# IMX8_INTERFACE.net
KiCad netlist of a schematic drawn in Altium Designer
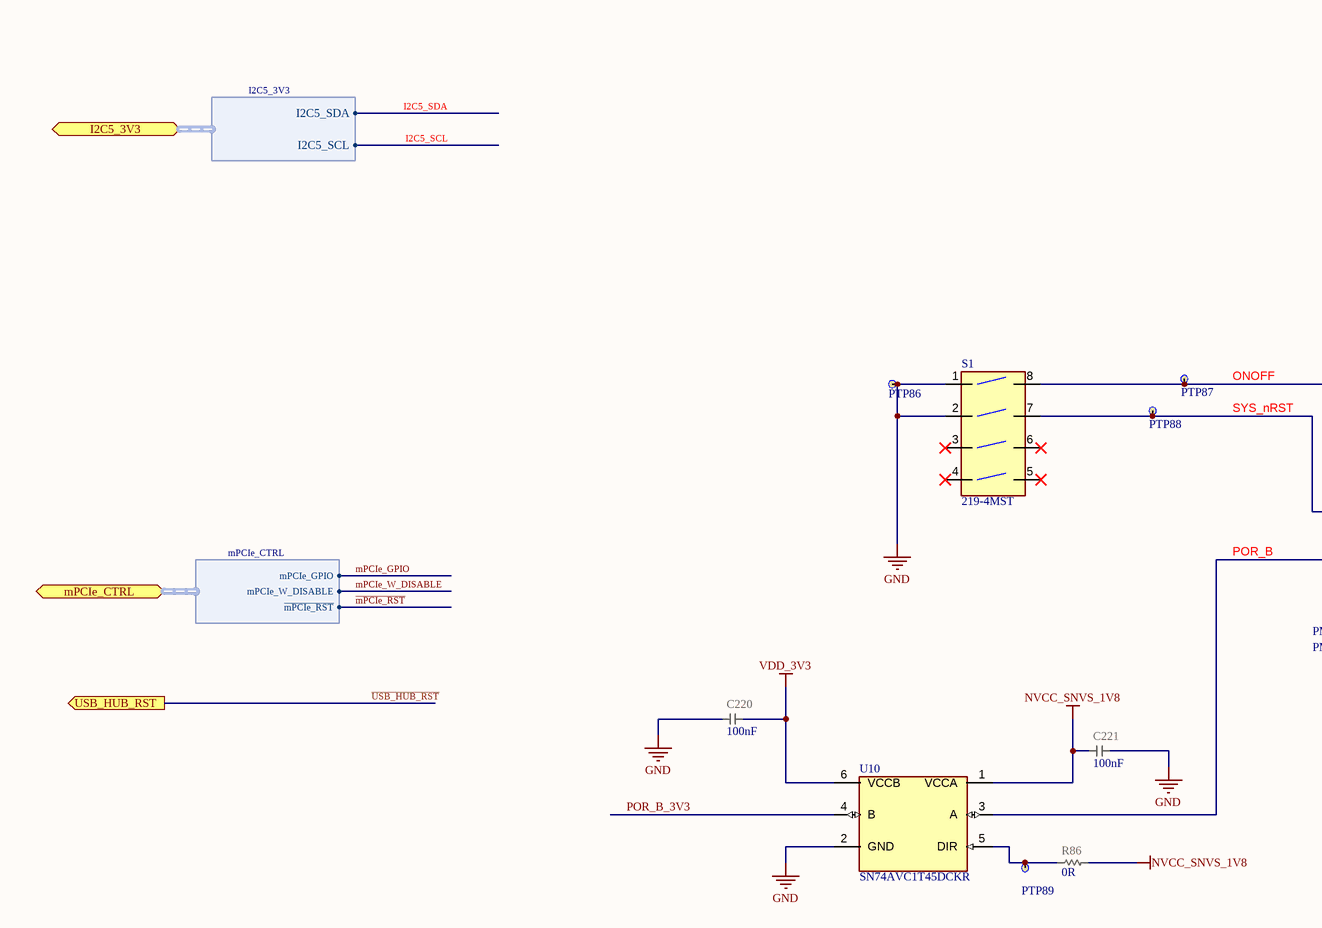
[diagram p0: IMX8_INTERFACE.SchDoc, top left]
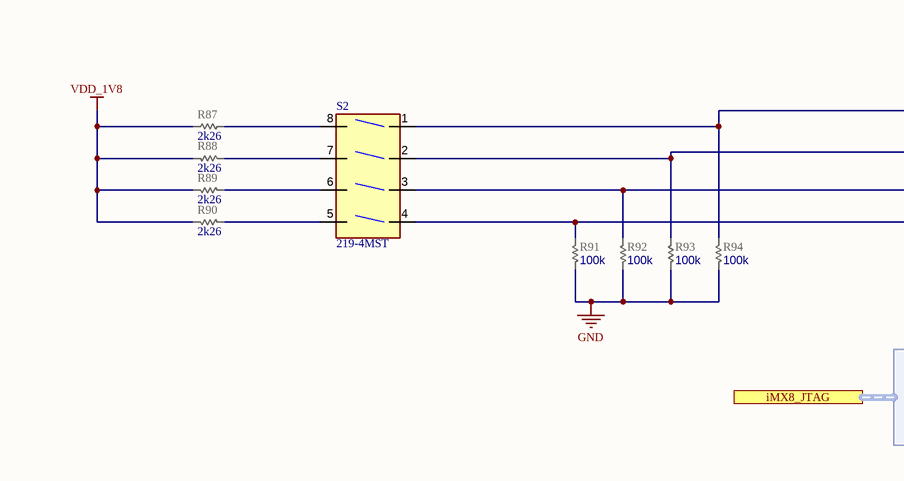
[diagram p1: IMX8_INTERFACE.SchDoc, bottom left]
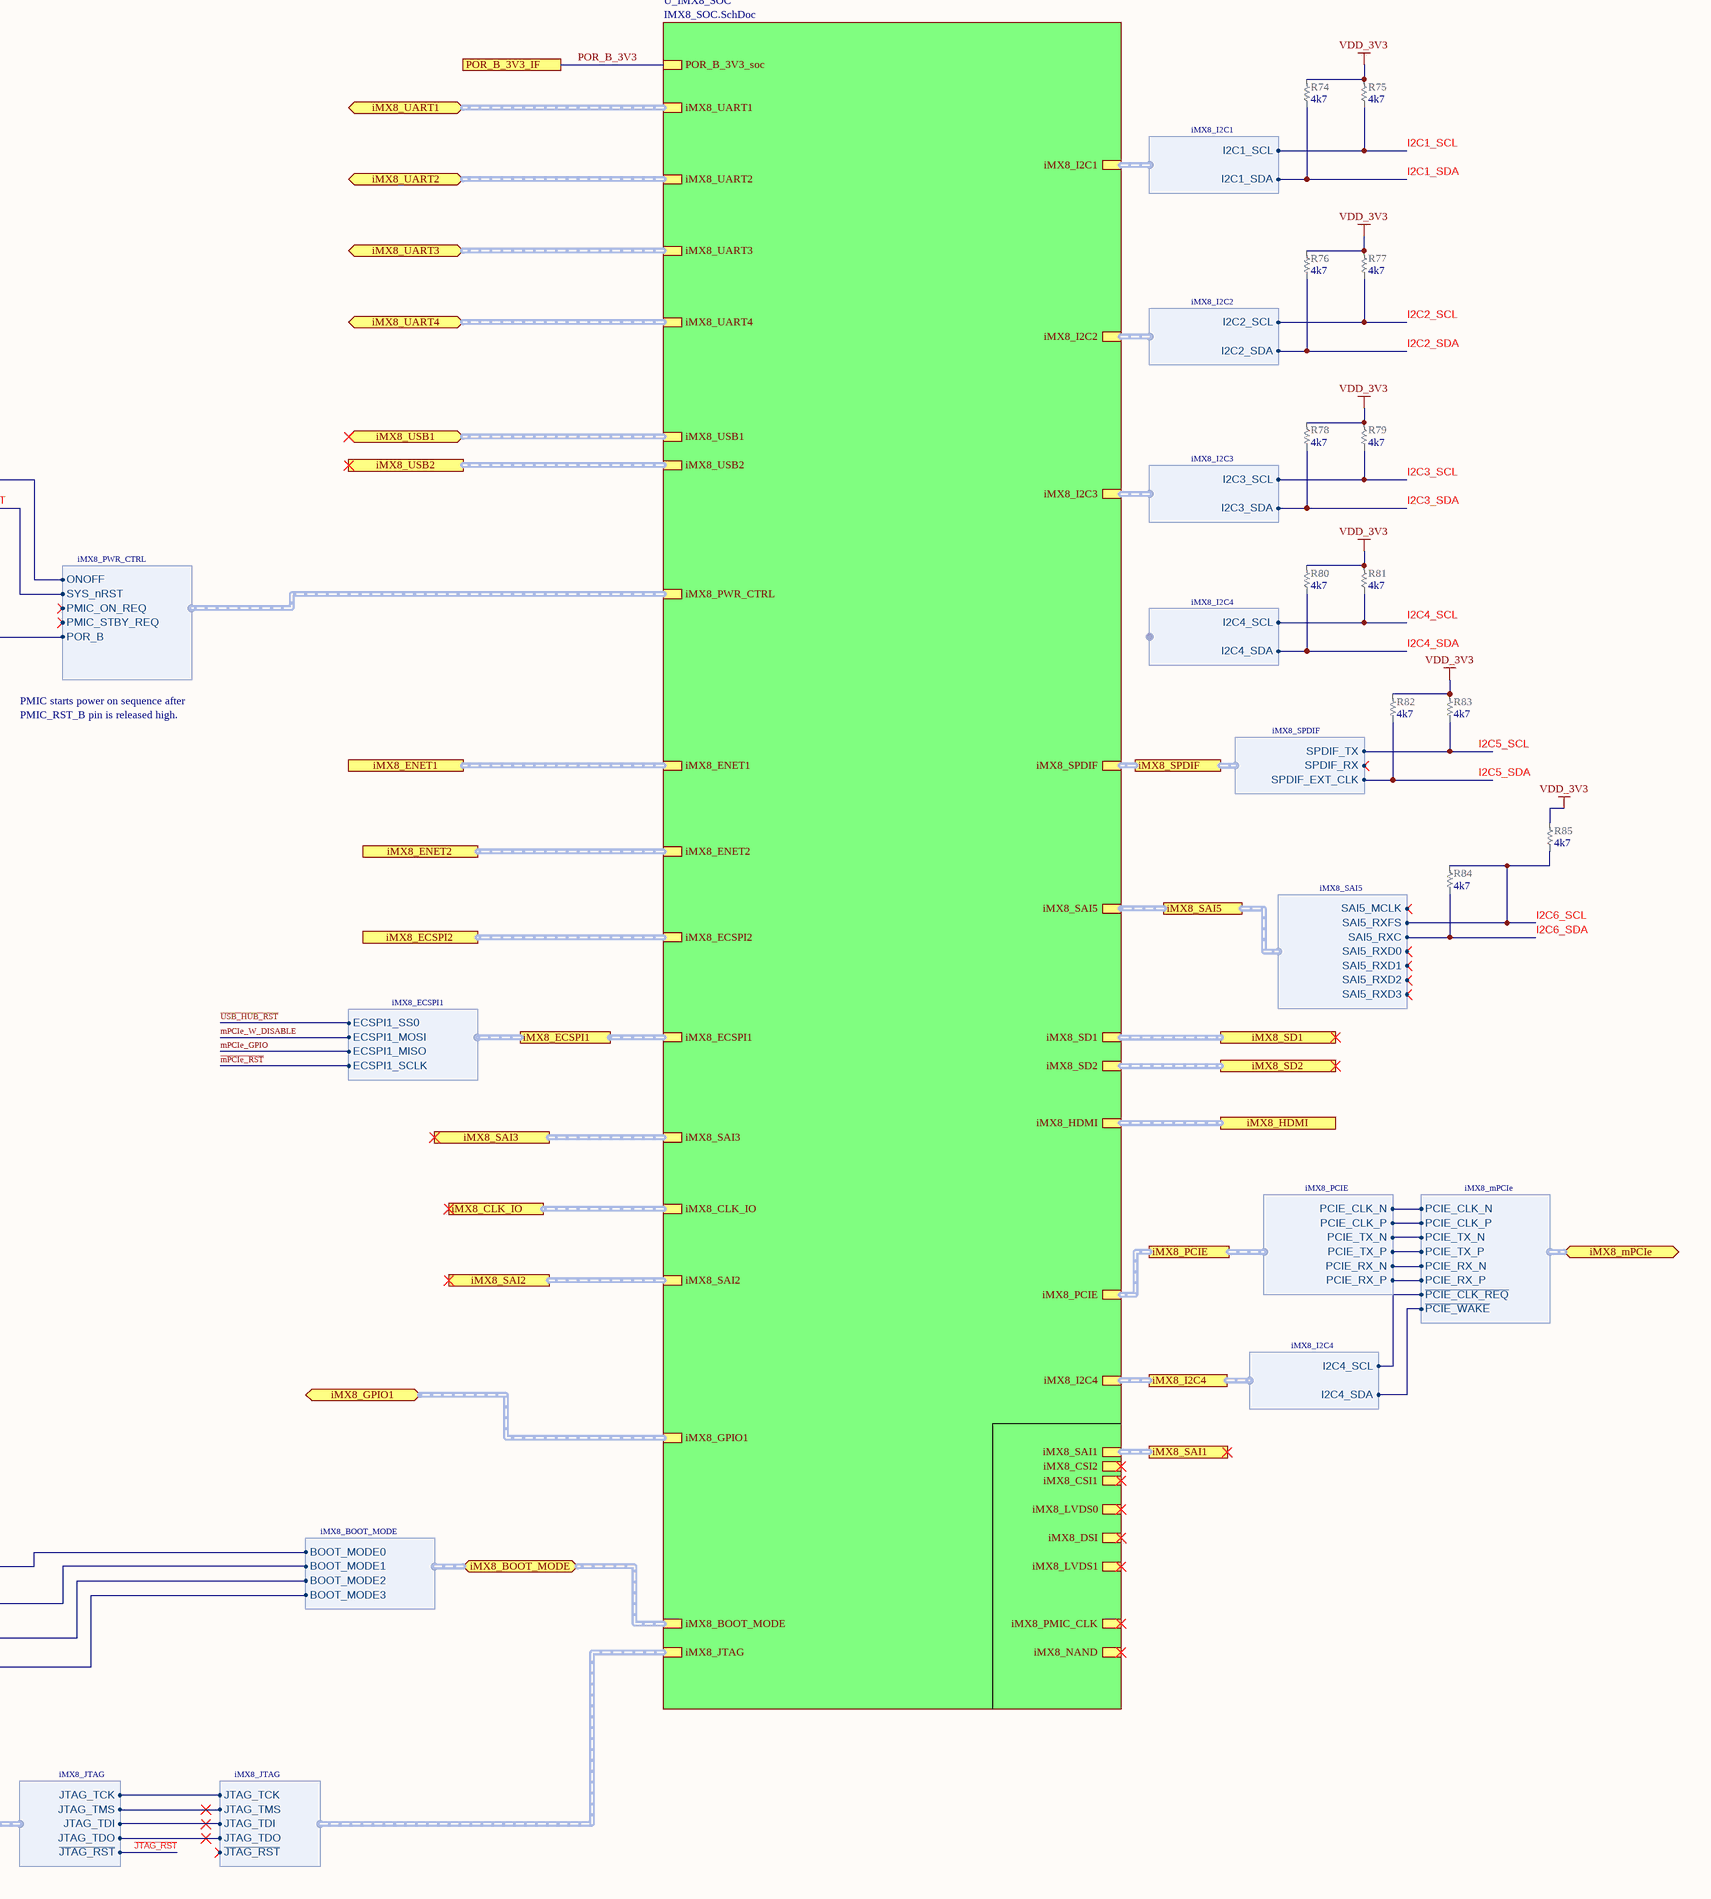
[diagram p2: IMX8_INTERFACE.SchDoc, bottom right]

(export (version "E")
  (design (tool "Eeschema 10.0.6"))
  (components
    (comp (ref "C220")
      (value "100nF")
      (footprint "CAP_0201_UN1Q")
      (description "CAP")
      (fields (field (name "PART NUMBER") "GRM033C71C104KE14D") (field (name "MANUFACTURER") "Murata"))
      (libsource (lib "robo_cam") (part "CMP-001-000385-16"))
    )
    (comp (ref "C221")
      (value "100nF")
      (footprint "CAP_0201_UN1Q")
      (description "CAP")
      (fields (field (name "PART NUMBER") "GRM033C71C104KE14D") (field (name "MANUFACTURER") "Murata"))
      (libsource (lib "robo_cam") (part "CMP-001-000385-16"))
    )
    (comp (ref "PTP86")
      (value "PTP_0.4mm")
      (footprint "PTP_0.4mm")
      (description "Production Testpoint 0.4mm. Flying probe. Use 1mm pitch.")
      (fields (field (name "PART NUMBER") "PTP 0.4mm"))
      (libsource (lib "robo_cam") (part "CMP-001-001296-3"))
    )
    (comp (ref "PTP87")
      (value "PTP_0.4mm")
      (footprint "PTP_0.4mm")
      (description "Production Testpoint 0.4mm. Flying probe. Use 1mm pitch.")
      (fields (field (name "PART NUMBER") "PTP 0.4mm"))
      (libsource (lib "robo_cam") (part "CMP-001-001296-3"))
    )
    (comp (ref "PTP88")
      (value "PTP_0.4mm")
      (footprint "PTP_0.4mm")
      (description "Production Testpoint 0.4mm. Flying probe. Use 1mm pitch.")
      (fields (field (name "PART NUMBER") "PTP 0.4mm"))
      (libsource (lib "robo_cam") (part "CMP-001-001296-3"))
    )
    (comp (ref "PTP89")
      (value "PTP_0.4mm")
      (footprint "PTP_0.4mm")
      (description "Production Testpoint 0.4mm. Flying probe. Use 1mm pitch.")
      (fields (field (name "PART NUMBER") "PTP 0.4mm"))
      (libsource (lib "robo_cam") (part "CMP-001-001296-3"))
    )
    (comp (ref "R74")
      (value "4k7")
      (footprint "RES_0201_UN1Q")
      (description "RES")
      (fields (field (name "PART NUMBER") "RC0201FR-074K7L") (field (name "MANUFACTURER") "YAGEO"))
      (libsource (lib "CM5_library") (part "CMP-001-000475-13"))
    )
    (comp (ref "R75")
      (value "4k7")
      (footprint "RES_0201_UN1Q")
      (description "RES")
      (fields (field (name "PART NUMBER") "RC0201FR-074K7L") (field (name "MANUFACTURER") "YAGEO"))
      (libsource (lib "CM5_library") (part "CMP-001-000475-13"))
    )
    (comp (ref "R76")
      (value "4k7")
      (footprint "RES_0201_UN1Q")
      (description "RES")
      (fields (field (name "PART NUMBER") "RC0201FR-074K7L") (field (name "MANUFACTURER") "YAGEO"))
      (libsource (lib "CM5_library") (part "CMP-001-000475-13"))
    )
    (comp (ref "R77")
      (value "4k7")
      (footprint "RES_0201_UN1Q")
      (description "RES")
      (fields (field (name "PART NUMBER") "RC0201FR-074K7L") (field (name "MANUFACTURER") "YAGEO"))
      (libsource (lib "CM5_library") (part "CMP-001-000475-13"))
    )
    (comp (ref "R78")
      (value "4k7")
      (footprint "RES_0201_UN1Q")
      (description "RES")
      (fields (field (name "PART NUMBER") "RC0201FR-074K7L") (field (name "MANUFACTURER") "YAGEO"))
      (libsource (lib "CM5_library") (part "CMP-001-000475-13"))
    )
    (comp (ref "R79")
      (value "4k7")
      (footprint "RES_0201_UN1Q")
      (description "RES")
      (fields (field (name "PART NUMBER") "RC0201FR-074K7L") (field (name "MANUFACTURER") "YAGEO"))
      (libsource (lib "CM5_library") (part "CMP-001-000475-13"))
    )
    (comp (ref "R80")
      (value "4k7")
      (footprint "RES_0201_UN1Q")
      (description "RES")
      (fields (field (name "PART NUMBER") "RC0201FR-074K7L") (field (name "MANUFACTURER") "YAGEO"))
      (libsource (lib "CM5_library") (part "CMP-001-000475-13"))
    )
    (comp (ref "R81")
      (value "4k7")
      (footprint "RES_0201_UN1Q")
      (description "RES")
      (fields (field (name "PART NUMBER") "RC0201FR-074K7L") (field (name "MANUFACTURER") "YAGEO"))
      (libsource (lib "CM5_library") (part "CMP-001-000475-13"))
    )
    (comp (ref "R82")
      (value "4k7")
      (footprint "RES_0201_UN1Q")
      (description "RES")
      (fields (field (name "PART NUMBER") "RC0201FR-074K7L") (field (name "MANUFACTURER") "YAGEO"))
      (libsource (lib "CM5_library") (part "CMP-001-000475-13"))
    )
    (comp (ref "R83")
      (value "4k7")
      (footprint "RES_0201_UN1Q")
      (description "RES")
      (fields (field (name "PART NUMBER") "RC0201FR-074K7L") (field (name "MANUFACTURER") "YAGEO"))
      (libsource (lib "CM5_library") (part "CMP-001-000475-13"))
    )
    (comp (ref "R84")
      (value "4k7")
      (footprint "RES_0201_UN1Q")
      (description "RES")
      (fields (field (name "PART NUMBER") "RC0201FR-074K7L") (field (name "MANUFACTURER") "YAGEO"))
      (libsource (lib "CM5_library") (part "CMP-001-000475-13"))
    )
    (comp (ref "R85")
      (value "4k7")
      (footprint "RES_0201_UN1Q")
      (description "RES")
      (fields (field (name "PART NUMBER") "RC0201FR-074K7L") (field (name "MANUFACTURER") "YAGEO"))
      (libsource (lib "CM5_library") (part "CMP-001-000475-13"))
    )
    (comp (ref "R86")
      (value "0R")
      (footprint "RES_0201_UN1Q")
      (description "RES")
      (fields (field (name "PART NUMBER") "RC0201JR-070RL") (field (name "MANUFACTURER") "YAGEO"))
      (libsource (lib "CM5_library") (part "CMP-001-000429-13"))
    )
    (comp (ref "R87")
      (value "2k26")
      (footprint "RES_0201_UN1Q")
      (description "RES")
      (fields (field (name "TOLERANCE") "1%") (field (name "MANUFACTURER") "YAGEO"))
      (libsource (lib "CM5_library") (part "CMP-001-001013-2"))
    )
    (comp (ref "R88")
      (value "2k26")
      (footprint "RES_0201_UN1Q")
      (description "RES")
      (fields (field (name "TOLERANCE") "1%") (field (name "MANUFACTURER") "YAGEO"))
      (libsource (lib "CM5_library") (part "CMP-001-001013-2"))
    )
    (comp (ref "R89")
      (value "2k26")
      (footprint "RES_0201_UN1Q")
      (description "RES")
      (fields (field (name "TOLERANCE") "1%") (field (name "MANUFACTURER") "YAGEO"))
      (libsource (lib "CM5_library") (part "CMP-001-001013-2"))
    )
    (comp (ref "R90")
      (value "2k26")
      (footprint "RES_0201_UN1Q")
      (description "RES")
      (fields (field (name "TOLERANCE") "1%") (field (name "MANUFACTURER") "YAGEO"))
      (libsource (lib "CM5_library") (part "CMP-001-001013-2"))
    )
    (comp (ref "R91")
      (value "100k")
      (footprint "RES_0201_UN1Q")
      (description "RES")
      (fields (field (name "TOLERANCE") "1%") (field (name "PART NUMBER") "RC0201FR-07100KL"))
      (libsource (lib "CM5_library") (part "CMP-001-000526-11"))
    )
    (comp (ref "R92")
      (value "100k")
      (footprint "RES_0201_UN1Q")
      (description "RES")
      (fields (field (name "TOLERANCE") "1%") (field (name "PART NUMBER") "RC0201FR-07100KL"))
      (libsource (lib "CM5_library") (part "CMP-001-000526-11"))
    )
    (comp (ref "R93")
      (value "100k")
      (footprint "RES_0201_UN1Q")
      (description "RES")
      (fields (field (name "TOLERANCE") "1%") (field (name "PART NUMBER") "RC0201FR-07100KL"))
      (libsource (lib "CM5_library") (part "CMP-001-000526-11"))
    )
    (comp (ref "R94")
      (value "100k")
      (footprint "RES_0201_UN1Q")
      (description "RES")
      (fields (field (name "TOLERANCE") "1%") (field (name "PART NUMBER") "RC0201FR-07100KL"))
      (libsource (lib "CM5_library") (part "CMP-001-000526-11"))
    )
    (comp (ref "S1")
      (value "219-4MST")
      (footprint "SW_219-4MST")
      (description "Dip Switch SPST 4 Position Surface Mount Slide (Standard) Actuator 100mA 20VDC")
      (fields (field (name "MF") "CTS Electrocomponents"))
      (libsource (lib "219-4MST") (part "219-4MST"))
    )
    (comp (ref "S2")
      (value "219-4MST")
      (footprint "SW_219-4MST")
      (description "Dip Switch SPST 4 Position Surface Mount Slide (Standard) Actuator 100mA 20VDC")
      (fields (field (name "MF") "CTS Electrocomponents"))
      (libsource (lib "") (part "219-4MST_1"))
    )
    (comp (ref "U10")
      (value "SN74AVC1T45DCKR")
      (footprint "SOT65P210X110-6N")
      (fields (field (name "MF") "Texas Instruments"))
      (libsource (lib "SN74AVC1T45DCKR") (part "SN74AVC1T45DCKR"))
    )
  )
  (nets
    (net (code "31") (name "/I2C1_SCL") (class "Default")
      (node (ref "R75") (pin "1") (pinfunction "1_1") (pintype "passive"))
    )
    (net (code "32") (name "/I2C1_SDA") (class "Default")
      (node (ref "R74") (pin "1") (pinfunction "1_1") (pintype "passive"))
    )
    (net (code "33") (name "/I2C2_SCL") (class "Default")
      (node (ref "R77") (pin "1") (pinfunction "1_1") (pintype "passive"))
    )
    (net (code "34") (name "/I2C2_SDA") (class "Default")
      (node (ref "R76") (pin "1") (pinfunction "1_1") (pintype "passive"))
    )
    (net (code "35") (name "/I2C3_SCL") (class "Default")
      (node (ref "R79") (pin "1") (pinfunction "1_1") (pintype "passive"))
    )
    (net (code "36") (name "/I2C3_SDA") (class "Default")
      (node (ref "R78") (pin "1") (pinfunction "1_1") (pintype "passive"))
    )
    (net (code "37") (name "/I2C4_SCL") (class "Default")
      (node (ref "R81") (pin "1") (pinfunction "1_1") (pintype "passive"))
    )
    (net (code "38") (name "/I2C4_SDA") (class "Default")
      (node (ref "R80") (pin "1") (pinfunction "1_1") (pintype "passive"))
    )
    (net (code "39") (name "/I2C5_SCL") (class "Default")
      (node (ref "R83") (pin "1") (pinfunction "1_1") (pintype "passive"))
    )
    (net (code "40") (name "/I2C5_SDA") (class "Default")
      (node (ref "R82") (pin "1") (pinfunction "1_1") (pintype "passive"))
    )
    (net (code "41") (name "/I2C6_SCL") (class "Default")
      (node (ref "R84") (pin "2") (pinfunction "2_2") (pintype "passive"))
      (node (ref "R85") (pin "1") (pinfunction "1_1") (pintype "passive"))
    )
    (net (code "42") (name "/I2C6_SDA") (class "Default")
      (node (ref "R84") (pin "1") (pinfunction "1_1") (pintype "passive"))
    )
    (net (code "44") (name "/ONOFF") (class "Default")
      (node (ref "PTP87") (pin "1") (pinfunction "TP_1") (pintype "passive"))
      (node (ref "S1") (pin "8") (pinfunction "8_8") (pintype "passive"))
    )
    (net (code "45") (name "/POR_B") (class "Default")
      (node (ref "U10") (pin "3") (pinfunction "A_3") (pintype "bidirectional"))
    )
    (net (code "46") (name "/POR_B_3V3") (class "Default")
      (node (ref "U10") (pin "4") (pinfunction "B_4") (pintype "bidirectional"))
    )
    (net (code "47") (name "/SYS_nRST") (class "Default")
      (node (ref "PTP88") (pin "1") (pinfunction "TP_1") (pintype "passive"))
      (node (ref "S1") (pin "7") (pinfunction "7_7") (pintype "passive"))
    )
    (net (code "90") (name "GND") (class "Default")
      (node (ref "C220") (pin "1") (pinfunction "1_1") (pintype "passive"))
      (node (ref "C221") (pin "2") (pinfunction "2_2") (pintype "passive"))
      (node (ref "PTP86") (pin "1") (pinfunction "TP_1") (pintype "passive"))
      (node (ref "R91") (pin "1") (pinfunction "1_1") (pintype "passive"))
      (node (ref "R92") (pin "1") (pinfunction "1_1") (pintype "passive"))
      (node (ref "R93") (pin "1") (pinfunction "1_1") (pintype "passive"))
      (node (ref "R94") (pin "1") (pinfunction "1_1") (pintype "passive"))
      (node (ref "S1") (pin "1") (pinfunction "1_1") (pintype "passive"))
      (node (ref "S1") (pin "2") (pinfunction "2_2") (pintype "passive"))
      (node (ref "U10") (pin "2") (pinfunction "GND_2") (pintype "power_in"))
    )
    (net (code "91") (name "NVCC_SNVS_1V8") (class "Default")
      (node (ref "C221") (pin "1") (pinfunction "1_1") (pintype "passive"))
      (node (ref "R86") (pin "2") (pinfunction "2_2") (pintype "passive"))
      (node (ref "U10") (pin "1") (pinfunction "VCCA_1") (pintype "power_in"))
    )
    (net (code "92") (name "Net-(PTP89-TP)") (class "Default")
      (node (ref "PTP89") (pin "1") (pinfunction "TP_1") (pintype "passive"))
      (node (ref "R86") (pin "1") (pinfunction "1_1") (pintype "passive"))
      (node (ref "U10") (pin "5") (pinfunction "DIR_5") (pintype "input"))
    )
    (net (code "93") (name "Net-(R87-Pad2)") (class "Default")
      (node (ref "R87") (pin "2") (pinfunction "2_2") (pintype "passive"))
      (node (ref "S2") (pin "8") (pinfunction "8_8") (pintype "passive"))
    )
    (net (code "94") (name "Net-(R88-Pad2)") (class "Default")
      (node (ref "R88") (pin "2") (pinfunction "2_2") (pintype "passive"))
      (node (ref "S2") (pin "7") (pinfunction "7_7") (pintype "passive"))
    )
    (net (code "95") (name "Net-(R89-Pad2)") (class "Default")
      (node (ref "R89") (pin "2") (pinfunction "2_2") (pintype "passive"))
      (node (ref "S2") (pin "6") (pinfunction "6_6") (pintype "passive"))
    )
    (net (code "96") (name "Net-(R90-Pad2)") (class "Default")
      (node (ref "R90") (pin "2") (pinfunction "2_2") (pintype "passive"))
      (node (ref "S2") (pin "5") (pinfunction "5_5") (pintype "passive"))
    )
    (net (code "97") (name "Net-(R91-Pad2)") (class "Default")
      (node (ref "R91") (pin "2") (pinfunction "2_2") (pintype "passive"))
      (node (ref "S2") (pin "4") (pinfunction "4_4") (pintype "passive"))
    )
    (net (code "98") (name "Net-(R92-Pad2)") (class "Default")
      (node (ref "R92") (pin "2") (pinfunction "2_2") (pintype "passive"))
      (node (ref "S2") (pin "3") (pinfunction "3_3") (pintype "passive"))
    )
    (net (code "99") (name "Net-(R93-Pad2)") (class "Default")
      (node (ref "R93") (pin "2") (pinfunction "2_2") (pintype "passive"))
      (node (ref "S2") (pin "2") (pinfunction "2_2") (pintype "passive"))
    )
    (net (code "100") (name "Net-(R94-Pad2)") (class "Default")
      (node (ref "R94") (pin "2") (pinfunction "2_2") (pintype "passive"))
      (node (ref "S2") (pin "1") (pinfunction "1_1") (pintype "passive"))
    )
    (net (code "101") (name "VDD_1V8") (class "Default")
      (node (ref "R87") (pin "1") (pinfunction "1_1") (pintype "passive"))
      (node (ref "R88") (pin "1") (pinfunction "1_1") (pintype "passive"))
      (node (ref "R89") (pin "1") (pinfunction "1_1") (pintype "passive"))
      (node (ref "R90") (pin "1") (pinfunction "1_1") (pintype "passive"))
    )
    (net (code "102") (name "VDD_3V3") (class "Default")
      (node (ref "C220") (pin "2") (pinfunction "2_2") (pintype "passive"))
      (node (ref "R74") (pin "2") (pinfunction "2_2") (pintype "passive"))
      (node (ref "R75") (pin "2") (pinfunction "2_2") (pintype "passive"))
      (node (ref "R76") (pin "2") (pinfunction "2_2") (pintype "passive"))
      (node (ref "R77") (pin "2") (pinfunction "2_2") (pintype "passive"))
      (node (ref "R78") (pin "2") (pinfunction "2_2") (pintype "passive"))
      (node (ref "R79") (pin "2") (pinfunction "2_2") (pintype "passive"))
      (node (ref "R80") (pin "2") (pinfunction "2_2") (pintype "passive"))
      (node (ref "R81") (pin "2") (pinfunction "2_2") (pintype "passive"))
      (node (ref "R82") (pin "2") (pinfunction "2_2") (pintype "passive"))
      (node (ref "R83") (pin "2") (pinfunction "2_2") (pintype "passive"))
      (node (ref "R85") (pin "2") (pinfunction "2_2") (pintype "passive"))
      (node (ref "U10") (pin "6") (pinfunction "VCCB_6") (pintype "power_in"))
    )
    (net (code "103") (name "unconnected-(S1-Pad3)") (class "Default")
      (node (ref "S1") (pin "3") (pinfunction "3_3") (pintype "passive+no_connect"))
    )
    (net (code "104") (name "unconnected-(S1-Pad4)") (class "Default")
      (node (ref "S1") (pin "4") (pinfunction "4_4") (pintype "passive+no_connect"))
    )
    (net (code "105") (name "unconnected-(S1-Pad5)") (class "Default")
      (node (ref "S1") (pin "5") (pinfunction "5_5") (pintype "passive+no_connect"))
    )
    (net (code "106") (name "unconnected-(S1-Pad6)") (class "Default")
      (node (ref "S1") (pin "6") (pinfunction "6_6") (pintype "passive+no_connect"))
    )
  )
)
